# salo_controler.net
KiCad netlist of a schematic drawn in Altium Designer
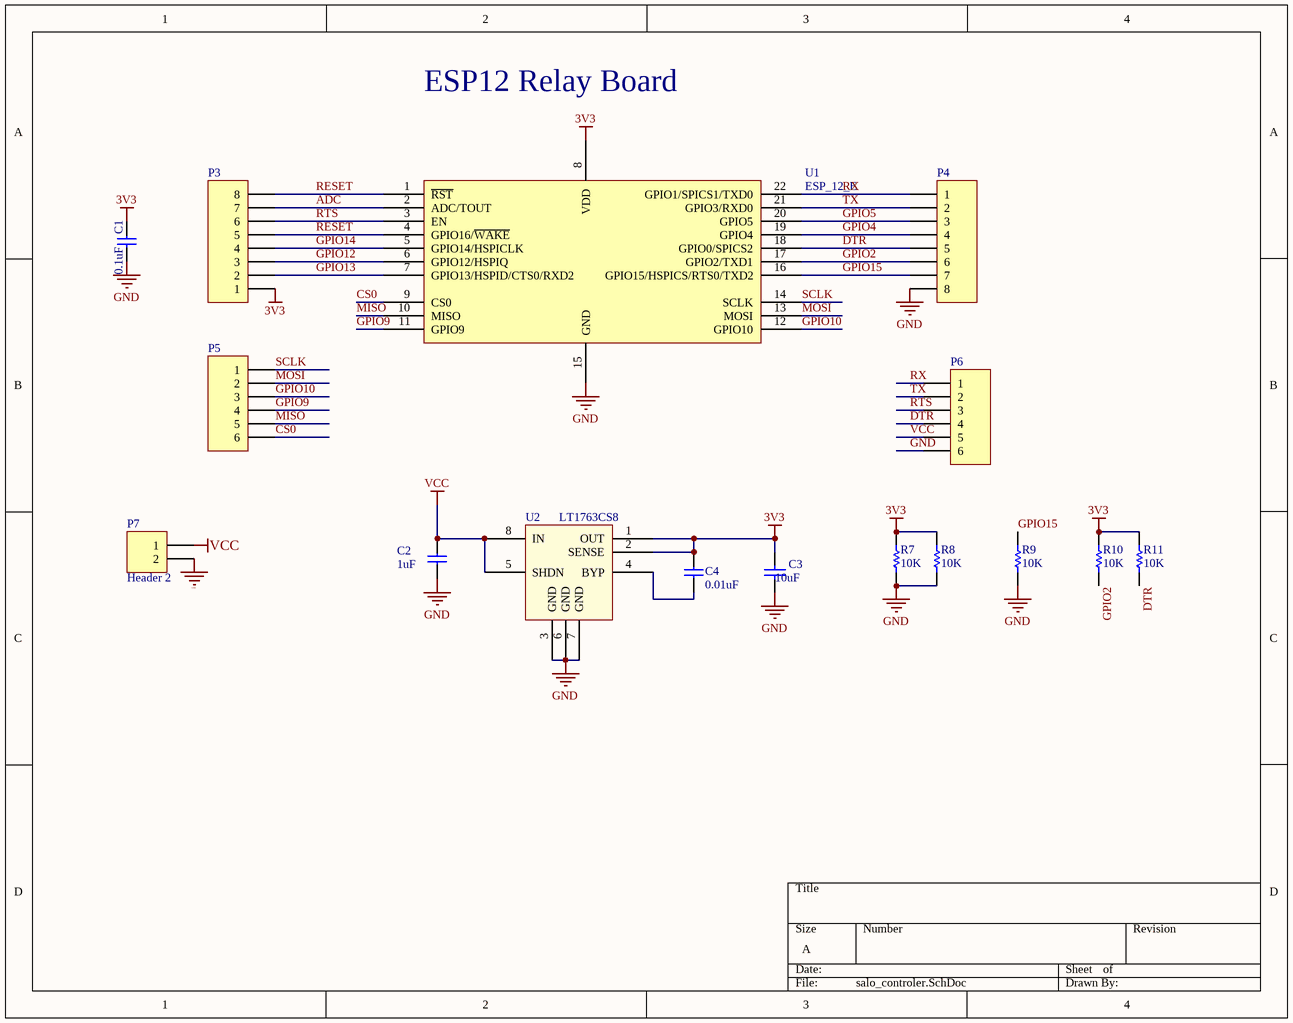
[diagram p0: salo_controler.SchDoc]

(export (version "E")
  (design (tool "Eeschema 10.0.6"))
  (components
    (comp (ref "C1")
      (value "0.1uF")
      (footprint "CAPC1608X06L")
      (description "Capacitor, X5R, ±10%")
      (fields (field (name "PART NUMBER") "C0603-4µ7") (field (name "PUBLISHER") "Nordic Semiconductor"))
      (libsource (lib "daniel_library") (part "CAP_0603"))
    )
    (comp (ref "C2")
      (value "1uF")
      (footprint "CAPC1608X06L")
      (description "Capacitor, X5R, ±10%")
      (fields (field (name "PART NUMBER") "C0603-4µ7") (field (name "PUBLISHER") "Nordic Semiconductor"))
      (libsource (lib "daniel_library") (part "CAP_0603"))
    )
    (comp (ref "C3")
      (value "10uF")
      (footprint "C0805")
      (description "Capacitor")
      (fields (field (name "Comment") "Cap"))
      (libsource (lib "Miscellaneous Devices") (part "Cap"))
    )
    (comp (ref "C4")
      (value "0.01uF")
      (footprint "CAPC1005X04L")
      (description "Capacitor, NP0, ±2%")
      (fields (field (name "PART NUMBER") "C0402-12p") (field (name "PUBLISHER") "Nordic Semiconductor"))
      (libsource (lib "daniel_library") (part "CAP_0402"))
    )
    (comp (ref "P3")
      (value "Header 8")
      (footprint "HDR1X8")
      (description "Header, 8-Pin")
      (fields (field (name "PUBLISHER") "Altium Limited"))
      (libsource (lib "") (part "Header 8_1"))
    )
    (comp (ref "P4")
      (value "Header 8")
      (footprint "HDR1X8")
      (description "Header, 8-Pin")
      (fields (field (name "PUBLISHER") "Altium Limited"))
      (libsource (lib "Miscellaneous Connectors") (part "Header 8"))
    )
    (comp (ref "P5")
      (value "Header 6")
      (footprint "HDR1X6")
      (description "Header, 6-Pin")
      (fields (field (name "PUBLISHER") "Altium Limited"))
      (libsource (lib "") (part "Header 6_1"))
    )
    (comp (ref "P6")
      (value "Header 6")
      (footprint "HDR1X6")
      (description "Header, 6-Pin")
      (fields (field (name "PUBLISHER") "Altium Limited"))
      (libsource (lib "Miscellaneous Connectors") (part "Header 6"))
    )
    (comp (ref "P7")
      (value "Header 2")
      (footprint "HDR1X2")
      (description "Header, 2-Pin")
      (fields (field (name "PUBLISHER") "Altium Limited"))
      (libsource (lib "Miscellaneous Connectors") (part "Header 2"))
    )
    (comp (ref "R7")
      (value "10K")
      (footprint "R0805")
      (description "Resistor")
      (fields (field (name "Comment") "Res1") (field (name "PUBLISHER") "Altium Limited"))
      (libsource (lib "Miscellaneous Devices") (part "Res1"))
    )
    (comp (ref "R8")
      (value "10K")
      (footprint "R0805")
      (description "Resistor")
      (fields (field (name "Comment") "Res1") (field (name "PUBLISHER") "Altium Limited"))
      (libsource (lib "Miscellaneous Devices") (part "Res1"))
    )
    (comp (ref "R9")
      (value "10K")
      (footprint "R0805")
      (description "Resistor")
      (fields (field (name "Comment") "Res1") (field (name "PUBLISHER") "Altium Limited"))
      (libsource (lib "Miscellaneous Devices") (part "Res1"))
    )
    (comp (ref "R10")
      (value "10K")
      (footprint "R0805")
      (description "Resistor")
      (fields (field (name "Comment") "Res1") (field (name "PUBLISHER") "Altium Limited"))
      (libsource (lib "Miscellaneous Devices") (part "Res1"))
    )
    (comp (ref "R11")
      (value "10K")
      (footprint "R0805")
      (description "Resistor")
      (fields (field (name "Comment") "Res1") (field (name "PUBLISHER") "Altium Limited"))
      (libsource (lib "Miscellaneous Devices") (part "Res1"))
    )
    (comp (ref "U1")
      (value "ESP_12_E")
      (footprint "ESP_12_E")
      (description "ESP-12 Wi-Fi Module by AI-Thinker")
      (libsource (lib "daniel_library") (part "ESP_12_E"))
    )
    (comp (ref "U2")
      (value "LT1763CS8")
      (footprint "SOIC8")
      (libsource (lib "daniel_library") (part "LT1763CS8"))
    )
  )
  (nets
    (net (code "1") (name "/ADC") (class "Default")
      (node (ref "P3") (pin "7") (pinfunction "7_7") (pintype "passive"))
      (node (ref "U1") (pin "2") (pinfunction "ADC/TOUT_2") (pintype "passive"))
    )
    (net (code "2") (name "/CS0") (class "Default")
      (node (ref "P5") (pin "6") (pinfunction "6_6") (pintype "passive"))
      (node (ref "U1") (pin "9") (pinfunction "CS0_9") (pintype "passive"))
    )
    (net (code "3") (name "/DTR") (class "Default")
      (node (ref "P4") (pin "5") (pinfunction "5_5") (pintype "passive"))
      (node (ref "P6") (pin "4") (pinfunction "4_4") (pintype "passive"))
      (node (ref "R11") (pin "1") (pinfunction "1_1") (pintype "passive"))
      (node (ref "U1") (pin "18") (pinfunction "GPIO0/SPICS2_18") (pintype "passive"))
    )
    (net (code "4") (name "/GPIO2") (class "Default")
      (node (ref "P4") (pin "6") (pinfunction "6_6") (pintype "passive"))
      (node (ref "R10") (pin "1") (pinfunction "1_1") (pintype "passive"))
      (node (ref "U1") (pin "17") (pinfunction "GPIO2/TXD1_17") (pintype "passive"))
    )
    (net (code "5") (name "/GPIO4") (class "Default")
      (node (ref "P4") (pin "4") (pinfunction "4_4") (pintype "passive"))
      (node (ref "U1") (pin "19") (pinfunction "GPIO4_19") (pintype "passive"))
    )
    (net (code "6") (name "/GPIO5") (class "Default")
      (node (ref "P4") (pin "3") (pinfunction "3_3") (pintype "passive"))
      (node (ref "U1") (pin "20") (pinfunction "GPIO5_20") (pintype "passive"))
    )
    (net (code "7") (name "/GPIO9") (class "Default")
      (node (ref "P5") (pin "4") (pinfunction "4_4") (pintype "passive"))
      (node (ref "U1") (pin "11") (pinfunction "GPIO9_11") (pintype "passive"))
    )
    (net (code "8") (name "/GPIO10") (class "Default")
      (node (ref "P5") (pin "3") (pinfunction "3_3") (pintype "passive"))
      (node (ref "U1") (pin "12") (pinfunction "GPIO10_12") (pintype "passive"))
    )
    (net (code "9") (name "/GPIO12") (class "Default")
      (node (ref "P3") (pin "3") (pinfunction "3_3") (pintype "passive"))
      (node (ref "U1") (pin "6") (pinfunction "GPIO12/HSPIQ_6") (pintype "passive"))
    )
    (net (code "10") (name "/GPIO13") (class "Default")
      (node (ref "P3") (pin "2") (pinfunction "2_2") (pintype "passive"))
      (node (ref "U1") (pin "7") (pinfunction "GPIO13/HSPID/CTS0/RXD2_7") (pintype "passive"))
    )
    (net (code "11") (name "/GPIO14") (class "Default")
      (node (ref "P3") (pin "4") (pinfunction "4_4") (pintype "passive"))
      (node (ref "U1") (pin "5") (pinfunction "GPIO14/HSPICLK_5") (pintype "passive"))
    )
    (net (code "12") (name "/GPIO15") (class "Default")
      (node (ref "P4") (pin "7") (pinfunction "7_7") (pintype "passive"))
      (node (ref "R9") (pin "2") (pinfunction "2_2") (pintype "passive"))
      (node (ref "U1") (pin "16") (pinfunction "GPIO15/HSPICS/RTS0/TXD2_16") (pintype "passive"))
    )
    (net (code "13") (name "/MISO") (class "Default")
      (node (ref "P5") (pin "5") (pinfunction "5_5") (pintype "passive"))
      (node (ref "U1") (pin "10") (pinfunction "MISO_10") (pintype "passive"))
    )
    (net (code "14") (name "/MOSI") (class "Default")
      (node (ref "P5") (pin "2") (pinfunction "2_2") (pintype "passive"))
      (node (ref "U1") (pin "13") (pinfunction "MOSI_13") (pintype "passive"))
    )
    (net (code "15") (name "/RESET") (class "Default")
      (node (ref "P3") (pin "5") (pinfunction "5_5") (pintype "passive"))
      (node (ref "P3") (pin "8") (pinfunction "8_8") (pintype "passive"))
      (node (ref "U1") (pin "1") (pinfunction "~{RST}_1") (pintype "passive"))
      (node (ref "U1") (pin "4") (pinfunction "GPIO16/~{WAKE}_4") (pintype "passive"))
    )
    (net (code "16") (name "/RTS") (class "Default")
      (node (ref "P3") (pin "6") (pinfunction "6_6") (pintype "passive"))
      (node (ref "P6") (pin "3") (pinfunction "3_3") (pintype "passive"))
      (node (ref "U1") (pin "3") (pinfunction "EN_3") (pintype "passive"))
    )
    (net (code "17") (name "/RX") (class "Default")
      (node (ref "P4") (pin "1") (pinfunction "1_1") (pintype "passive"))
      (node (ref "P6") (pin "1") (pinfunction "1_1") (pintype "passive"))
      (node (ref "U1") (pin "22") (pinfunction "GPIO1/SPICS1/TXD0_22") (pintype "passive"))
    )
    (net (code "18") (name "/SCLK") (class "Default")
      (node (ref "P5") (pin "1") (pinfunction "1_1") (pintype "passive"))
      (node (ref "U1") (pin "14") (pinfunction "SCLK_14") (pintype "passive"))
    )
    (net (code "19") (name "/TX") (class "Default")
      (node (ref "P4") (pin "2") (pinfunction "2_2") (pintype "passive"))
      (node (ref "P6") (pin "2") (pinfunction "2_2") (pintype "passive"))
      (node (ref "U1") (pin "21") (pinfunction "GPIO3/RXD0_21") (pintype "passive"))
    )
    (net (code "20") (name "3V3") (class "Default")
      (node (ref "C1") (pin "2") (pinfunction "2_2") (pintype "passive"))
      (node (ref "C3") (pin "2") (pinfunction "2_2") (pintype "passive"))
      (node (ref "C4") (pin "2") (pinfunction "2_2") (pintype "passive"))
      (node (ref "P3") (pin "1") (pinfunction "1_1") (pintype "passive"))
      (node (ref "R10") (pin "2") (pinfunction "2_2") (pintype "passive"))
      (node (ref "R11") (pin "2") (pinfunction "2_2") (pintype "passive"))
      (node (ref "R7") (pin "2") (pinfunction "2_2") (pintype "passive"))
      (node (ref "R8") (pin "2") (pinfunction "2_2") (pintype "passive"))
      (node (ref "U1") (pin "8") (pinfunction "VDD_8") (pintype "passive"))
      (node (ref "U2") (pin "1") (pinfunction "OUT_1") (pintype "passive"))
      (node (ref "U2") (pin "2") (pinfunction "SENSE_2") (pintype "passive"))
    )
    (net (code "21") (name "GND") (class "Default")
      (node (ref "C1") (pin "1") (pinfunction "1_1") (pintype "passive"))
      (node (ref "C2") (pin "1") (pinfunction "1_1") (pintype "passive"))
      (node (ref "C3") (pin "1") (pinfunction "1_1") (pintype "passive"))
      (node (ref "P4") (pin "8") (pinfunction "8_8") (pintype "passive"))
      (node (ref "P6") (pin "6") (pinfunction "6_6") (pintype "passive"))
      (node (ref "P7") (pin "2") (pinfunction "2_2") (pintype "passive"))
      (node (ref "R7") (pin "1") (pinfunction "1_1") (pintype "passive"))
      (node (ref "R8") (pin "1") (pinfunction "1_1") (pintype "passive"))
      (node (ref "R9") (pin "1") (pinfunction "1_1") (pintype "passive"))
      (node (ref "U1") (pin "15") (pinfunction "GND_15") (pintype "passive"))
      (node (ref "U2") (pin "3") (pinfunction "GND_3") (pintype "passive"))
      (node (ref "U2") (pin "6") (pinfunction "GND_6") (pintype "passive"))
      (node (ref "U2") (pin "7") (pinfunction "GND_7") (pintype "passive"))
    )
    (net (code "22") (name "Net-(U2-BYP)") (class "Default")
      (node (ref "C4") (pin "1") (pinfunction "1_1") (pintype "passive"))
      (node (ref "U2") (pin "4") (pinfunction "BYP_4") (pintype "passive"))
    )
    (net (code "23") (name "VCC") (class "Default")
      (node (ref "C2") (pin "2") (pinfunction "2_2") (pintype "passive"))
      (node (ref "P6") (pin "5") (pinfunction "5_5") (pintype "passive"))
      (node (ref "P7") (pin "1") (pinfunction "1_1") (pintype "passive"))
      (node (ref "U2") (pin "5") (pinfunction "SHDN_5") (pintype "passive"))
      (node (ref "U2") (pin "8") (pinfunction "IN_8") (pintype "passive"))
    )
  )
)
